# dual_sampler-GND-added.net
KiCad netlist of a schematic drawn in EAGLE
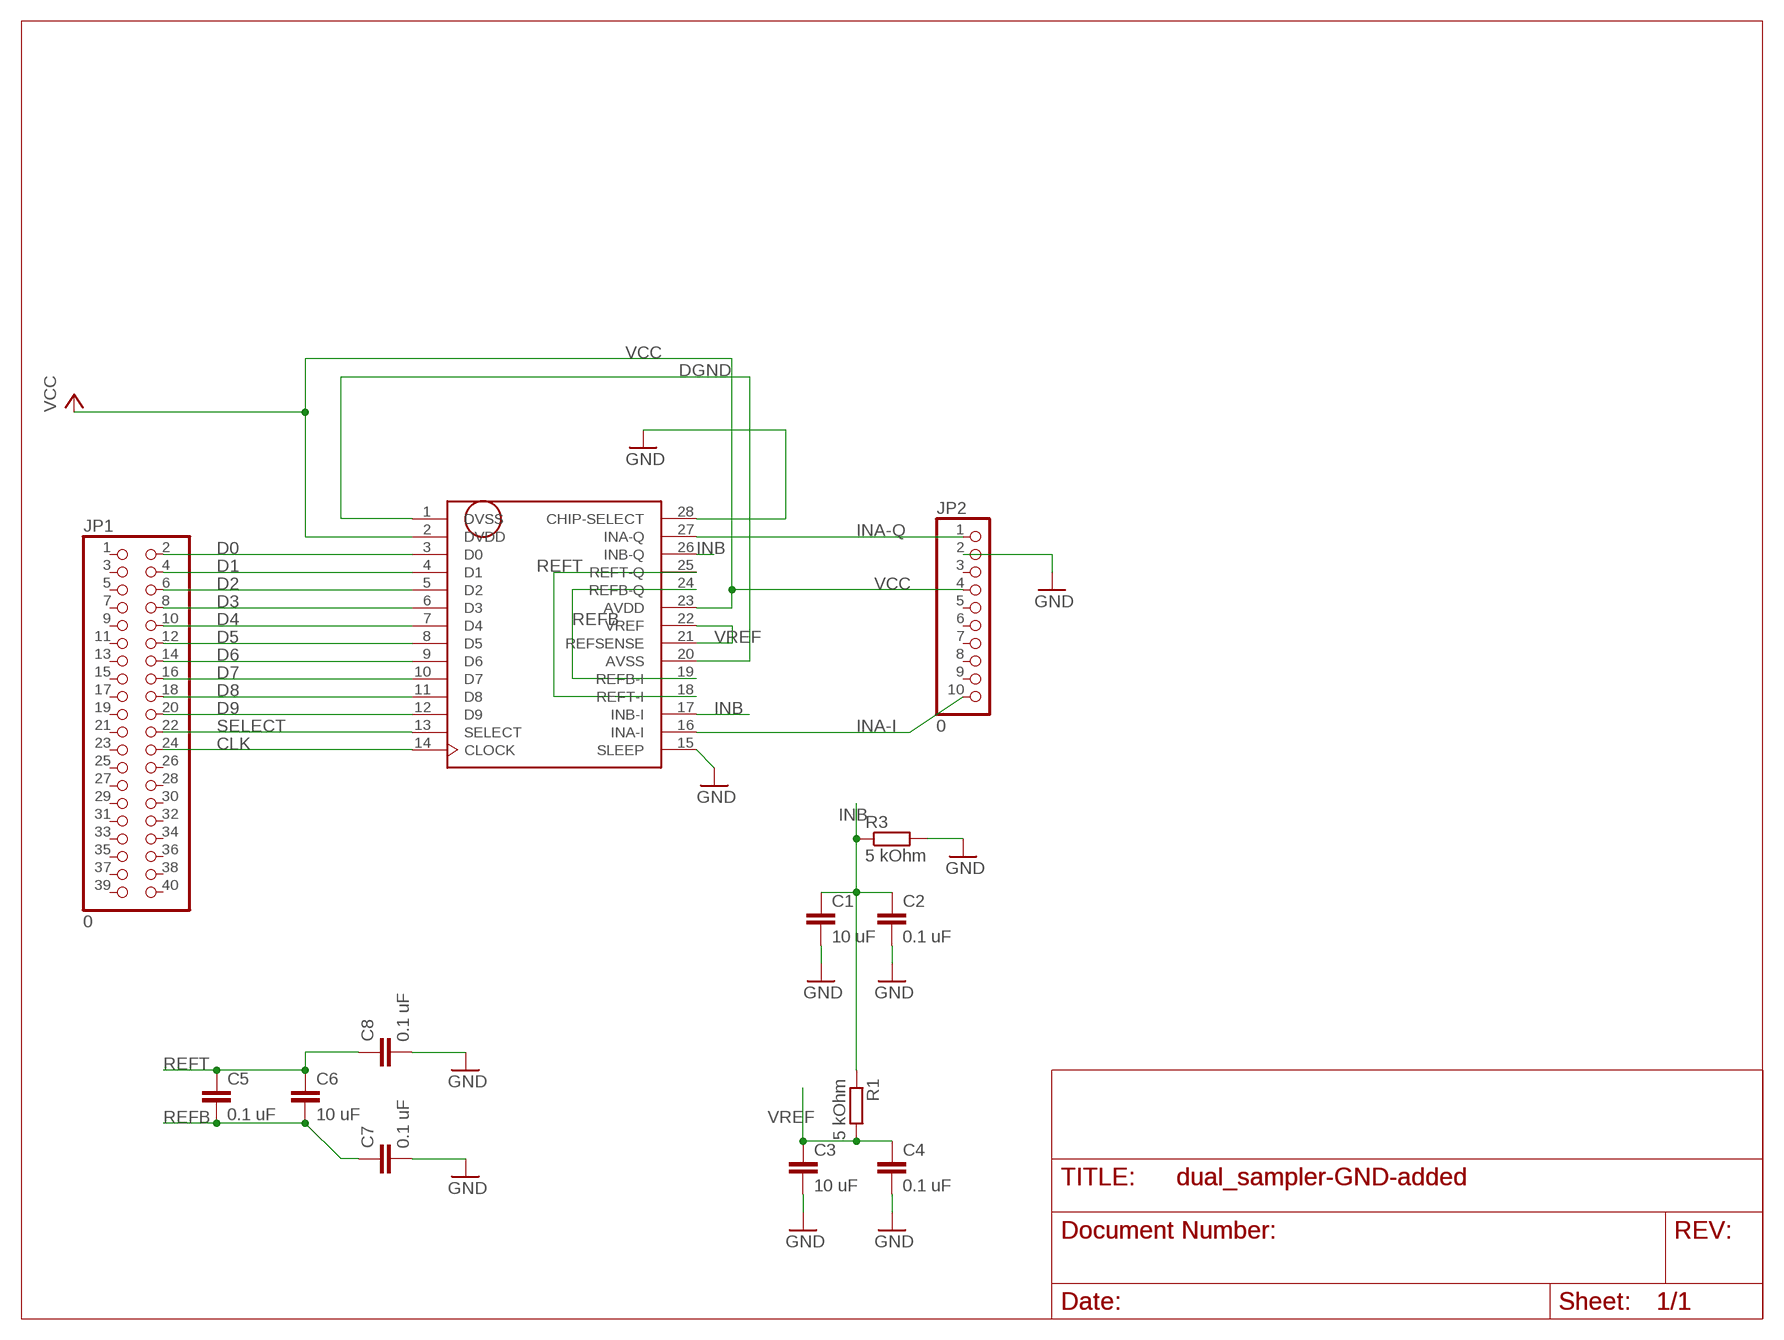
[diagram p0: schematic, sheet 1]

(export (version "E")
  (design (tool "Eeschema 10.0.6"))
  (components
    (comp (ref "C1")
      (value "10 uF")
      (footprint "eagle-import:C2.5-3")
      (libsource (lib "eagle-import") (part "C2,5-3"))
    )
    (comp (ref "C2")
      (value "0.1 uF")
      (footprint "eagle-import:C2.5-3")
      (libsource (lib "eagle-import") (part "C2,5-3"))
    )
    (comp (ref "C3")
      (value "10 uF")
      (footprint "eagle-import:C2.5-3")
      (libsource (lib "eagle-import") (part "C2,5-3"))
    )
    (comp (ref "C4")
      (value "0.1 uF")
      (footprint "eagle-import:C2.5-3")
      (libsource (lib "eagle-import") (part "C2,5-3"))
    )
    (comp (ref "C5")
      (value "0.1 uF")
      (footprint "eagle-import:C2.5-3")
      (libsource (lib "eagle-import") (part "C2,5-3"))
    )
    (comp (ref "C6")
      (value "10 uF")
      (footprint "eagle-import:C2.5-3")
      (libsource (lib "eagle-import") (part "C2,5-3"))
    )
    (comp (ref "C7")
      (value "0.1 uF")
      (footprint "eagle-import:C2.5-3")
      (libsource (lib "eagle-import") (part "C2,5-3"))
    )
    (comp (ref "C8")
      (value "0.1 uF")
      (footprint "eagle-import:C2.5-3")
      (libsource (lib "eagle-import") (part "C2,5-3"))
    )
    (comp (ref "JP1")
      (value "0")
      (footprint "eagle-import:2X20")
      (libsource (lib "eagle-import") (part "PINHD-2X20"))
    )
    (comp (ref "JP2")
      (value "0")
      (footprint "eagle-import:1X10")
      (libsource (lib "eagle-import") (part "PINHD-1X10"))
    )
    (comp (ref "R1")
      (value "5 kOhm")
      (footprint "eagle-import:0204_7")
      (libsource (lib "eagle-import") (part "R-EU_0204/7"))
    )
    (comp (ref "R3")
      (value "5 kOhm")
      (footprint "eagle-import:0204_7")
      (libsource (lib "eagle-import") (part "R-EU_0204/7"))
    )
    (comp (ref "U$1")
      (value "AD9201ARSZ")
      (footprint "eagle-import:SSOP28")
      (libsource (lib "eagle-import") (part "AD9201ARSZ"))
    )
  )
  (nets
    (net (code "1") (name "/CLK") (class "Default")
      (node (ref "JP1") (pin "24") (pinfunction "24_24") (pintype "passive"))
      (node (ref "U$1") (pin "14") (pinfunction "CLOCK_14") (pintype "input"))
    )
    (net (code "2") (name "/D0") (class "Default")
      (node (ref "JP1") (pin "2") (pinfunction "2_2") (pintype "passive"))
      (node (ref "U$1") (pin "3") (pinfunction "D0_3") (pintype "output"))
    )
    (net (code "3") (name "/D1") (class "Default")
      (node (ref "JP1") (pin "4") (pinfunction "4_4") (pintype "passive"))
      (node (ref "U$1") (pin "4") (pinfunction "D1_4") (pintype "output"))
    )
    (net (code "4") (name "/D2") (class "Default")
      (node (ref "JP1") (pin "6") (pinfunction "6_6") (pintype "passive"))
      (node (ref "U$1") (pin "5") (pinfunction "D2_5") (pintype "output"))
    )
    (net (code "5") (name "/D3") (class "Default")
      (node (ref "JP1") (pin "8") (pinfunction "8_8") (pintype "passive"))
      (node (ref "U$1") (pin "6") (pinfunction "D3_6") (pintype "output"))
    )
    (net (code "6") (name "/D4") (class "Default")
      (node (ref "JP1") (pin "10") (pinfunction "10_10") (pintype "passive"))
      (node (ref "U$1") (pin "7") (pinfunction "D4_7") (pintype "output"))
    )
    (net (code "7") (name "/D5") (class "Default")
      (node (ref "JP1") (pin "12") (pinfunction "12_12") (pintype "passive"))
      (node (ref "U$1") (pin "8") (pinfunction "D5_8") (pintype "output"))
    )
    (net (code "8") (name "/D6") (class "Default")
      (node (ref "JP1") (pin "14") (pinfunction "14_14") (pintype "passive"))
      (node (ref "U$1") (pin "9") (pinfunction "D6_9") (pintype "output"))
    )
    (net (code "9") (name "/D7") (class "Default")
      (node (ref "JP1") (pin "16") (pinfunction "16_16") (pintype "passive"))
      (node (ref "U$1") (pin "10") (pinfunction "D7_10") (pintype "output"))
    )
    (net (code "10") (name "/D8") (class "Default")
      (node (ref "JP1") (pin "18") (pinfunction "18_18") (pintype "passive"))
      (node (ref "U$1") (pin "11") (pinfunction "D8_11") (pintype "output"))
    )
    (net (code "11") (name "/D9") (class "Default")
      (node (ref "JP1") (pin "20") (pinfunction "20_20") (pintype "passive"))
      (node (ref "U$1") (pin "12") (pinfunction "D9_12") (pintype "output"))
    )
    (net (code "12") (name "/DGND") (class "Default")
      (node (ref "U$1") (pin "1") (pinfunction "DVSS_1") (pintype "power_in"))
      (node (ref "U$1") (pin "20") (pinfunction "AVSS_20") (pintype "input"))
    )
    (net (code "13") (name "/INA-I") (class "Default")
      (node (ref "JP2") (pin "10") (pinfunction "10_10") (pintype "passive"))
      (node (ref "U$1") (pin "16") (pinfunction "INA-I_16") (pintype "input"))
    )
    (net (code "14") (name "/INA-Q") (class "Default")
      (node (ref "JP2") (pin "1") (pinfunction "1_1") (pintype "passive"))
      (node (ref "U$1") (pin "27") (pinfunction "INA-Q_27") (pintype "input"))
    )
    (net (code "15") (name "/INB") (class "Default")
      (node (ref "C1") (pin "1") (pinfunction "1_1") (pintype "passive"))
      (node (ref "C2") (pin "1") (pinfunction "1_1") (pintype "passive"))
      (node (ref "R1") (pin "1") (pinfunction "1_1") (pintype "passive"))
      (node (ref "R3") (pin "1") (pinfunction "1_1") (pintype "passive"))
      (node (ref "U$1") (pin "17") (pinfunction "INB-I_17") (pintype "input"))
      (node (ref "U$1") (pin "26") (pinfunction "INB-Q_26") (pintype "input"))
    )
    (net (code "16") (name "/REFB") (class "Default")
      (node (ref "C5") (pin "2") (pinfunction "2_2") (pintype "passive"))
      (node (ref "C6") (pin "2") (pinfunction "2_2") (pintype "passive"))
      (node (ref "C7") (pin "1") (pinfunction "1_1") (pintype "passive"))
      (node (ref "U$1") (pin "19") (pinfunction "REFB-I_19") (pintype "bidirectional"))
      (node (ref "U$1") (pin "24") (pinfunction "REFB-Q_24") (pintype "input"))
    )
    (net (code "17") (name "/REFT") (class "Default")
      (node (ref "C5") (pin "1") (pinfunction "1_1") (pintype "passive"))
      (node (ref "C6") (pin "1") (pinfunction "1_1") (pintype "passive"))
      (node (ref "C8") (pin "1") (pinfunction "1_1") (pintype "passive"))
      (node (ref "U$1") (pin "18") (pinfunction "REFT-I_18") (pintype "input"))
      (node (ref "U$1") (pin "25") (pinfunction "REFT-Q_25") (pintype "input"))
    )
    (net (code "18") (name "/SELECT") (class "Default")
      (node (ref "JP1") (pin "22") (pinfunction "22_22") (pintype "passive"))
      (node (ref "U$1") (pin "13") (pinfunction "SELECT_13") (pintype "input"))
    )
    (net (code "19") (name "/VREF") (class "Default")
      (node (ref "C3") (pin "1") (pinfunction "1_1") (pintype "passive"))
      (node (ref "C4") (pin "1") (pinfunction "1_1") (pintype "passive"))
      (node (ref "R1") (pin "2") (pinfunction "2_2") (pintype "passive"))
      (node (ref "U$1") (pin "21") (pinfunction "REFSENSE_21") (pintype "input"))
      (node (ref "U$1") (pin "22") (pinfunction "VREF_22") (pintype "input"))
    )
    (net (code "20") (name "GND") (class "Default")
      (node (ref "C1") (pin "2") (pinfunction "2_2") (pintype "passive"))
      (node (ref "C2") (pin "2") (pinfunction "2_2") (pintype "passive"))
      (node (ref "C3") (pin "2") (pinfunction "2_2") (pintype "passive"))
      (node (ref "C4") (pin "2") (pinfunction "2_2") (pintype "passive"))
      (node (ref "C7") (pin "2") (pinfunction "2_2") (pintype "passive"))
      (node (ref "C8") (pin "2") (pinfunction "2_2") (pintype "passive"))
      (node (ref "JP2") (pin "2") (pinfunction "2_2") (pintype "passive"))
      (node (ref "R3") (pin "2") (pinfunction "2_2") (pintype "passive"))
      (node (ref "U$1") (pin "15") (pinfunction "SLEEP_15") (pintype "input"))
      (node (ref "U$1") (pin "28") (pinfunction "CHIP-SELECT_28") (pintype "input"))
    )
    (net (code "21") (name "VCC") (class "Default")
      (node (ref "JP2") (pin "4") (pinfunction "4_4") (pintype "passive"))
      (node (ref "U$1") (pin "2") (pinfunction "DVDD_2") (pintype "power_in"))
      (node (ref "U$1") (pin "23") (pinfunction "AVDD_23") (pintype "power_in"))
    )
    (net (code "22") (name "unconnected-(JP1-Pad1)") (class "Default")
      (node (ref "JP1") (pin "1") (pinfunction "1_1") (pintype "passive"))
    )
    (net (code "23") (name "unconnected-(JP1-Pad3)") (class "Default")
      (node (ref "JP1") (pin "3") (pinfunction "3_3") (pintype "passive"))
    )
    (net (code "24") (name "unconnected-(JP1-Pad5)") (class "Default")
      (node (ref "JP1") (pin "5") (pinfunction "5_5") (pintype "passive"))
    )
    (net (code "25") (name "unconnected-(JP1-Pad7)") (class "Default")
      (node (ref "JP1") (pin "7") (pinfunction "7_7") (pintype "passive"))
    )
    (net (code "26") (name "unconnected-(JP1-Pad9)") (class "Default")
      (node (ref "JP1") (pin "9") (pinfunction "9_9") (pintype "passive"))
    )
    (net (code "27") (name "unconnected-(JP1-Pad11)") (class "Default")
      (node (ref "JP1") (pin "11") (pinfunction "11_11") (pintype "passive"))
    )
    (net (code "28") (name "unconnected-(JP1-Pad13)") (class "Default")
      (node (ref "JP1") (pin "13") (pinfunction "13_13") (pintype "passive"))
    )
    (net (code "29") (name "unconnected-(JP1-Pad15)") (class "Default")
      (node (ref "JP1") (pin "15") (pinfunction "15_15") (pintype "passive"))
    )
    (net (code "30") (name "unconnected-(JP1-Pad17)") (class "Default")
      (node (ref "JP1") (pin "17") (pinfunction "17_17") (pintype "passive"))
    )
    (net (code "31") (name "unconnected-(JP1-Pad19)") (class "Default")
      (node (ref "JP1") (pin "19") (pinfunction "19_19") (pintype "passive"))
    )
    (net (code "32") (name "unconnected-(JP1-Pad21)") (class "Default")
      (node (ref "JP1") (pin "21") (pinfunction "21_21") (pintype "passive"))
    )
    (net (code "33") (name "unconnected-(JP1-Pad23)") (class "Default")
      (node (ref "JP1") (pin "23") (pinfunction "23_23") (pintype "passive"))
    )
    (net (code "34") (name "unconnected-(JP1-Pad25)") (class "Default")
      (node (ref "JP1") (pin "25") (pinfunction "25_25") (pintype "passive"))
    )
    (net (code "35") (name "unconnected-(JP1-Pad26)") (class "Default")
      (node (ref "JP1") (pin "26") (pinfunction "26_26") (pintype "passive"))
    )
    (net (code "36") (name "unconnected-(JP1-Pad27)") (class "Default")
      (node (ref "JP1") (pin "27") (pinfunction "27_27") (pintype "passive"))
    )
    (net (code "37") (name "unconnected-(JP1-Pad28)") (class "Default")
      (node (ref "JP1") (pin "28") (pinfunction "28_28") (pintype "passive"))
    )
    (net (code "38") (name "unconnected-(JP1-Pad29)") (class "Default")
      (node (ref "JP1") (pin "29") (pinfunction "29_29") (pintype "passive"))
    )
    (net (code "39") (name "unconnected-(JP1-Pad30)") (class "Default")
      (node (ref "JP1") (pin "30") (pinfunction "30_30") (pintype "passive"))
    )
    (net (code "40") (name "unconnected-(JP1-Pad31)") (class "Default")
      (node (ref "JP1") (pin "31") (pinfunction "31_31") (pintype "passive"))
    )
    (net (code "41") (name "unconnected-(JP1-Pad32)") (class "Default")
      (node (ref "JP1") (pin "32") (pinfunction "32_32") (pintype "passive"))
    )
    (net (code "42") (name "unconnected-(JP1-Pad33)") (class "Default")
      (node (ref "JP1") (pin "33") (pinfunction "33_33") (pintype "passive"))
    )
    (net (code "43") (name "unconnected-(JP1-Pad34)") (class "Default")
      (node (ref "JP1") (pin "34") (pinfunction "34_34") (pintype "passive"))
    )
    (net (code "44") (name "unconnected-(JP1-Pad35)") (class "Default")
      (node (ref "JP1") (pin "35") (pinfunction "35_35") (pintype "passive"))
    )
    (net (code "45") (name "unconnected-(JP1-Pad36)") (class "Default")
      (node (ref "JP1") (pin "36") (pinfunction "36_36") (pintype "passive"))
    )
    (net (code "46") (name "unconnected-(JP1-Pad37)") (class "Default")
      (node (ref "JP1") (pin "37") (pinfunction "37_37") (pintype "passive"))
    )
    (net (code "47") (name "unconnected-(JP1-Pad38)") (class "Default")
      (node (ref "JP1") (pin "38") (pinfunction "38_38") (pintype "passive"))
    )
    (net (code "48") (name "unconnected-(JP1-Pad39)") (class "Default")
      (node (ref "JP1") (pin "39") (pinfunction "39_39") (pintype "passive"))
    )
    (net (code "49") (name "unconnected-(JP1-Pad40)") (class "Default")
      (node (ref "JP1") (pin "40") (pinfunction "40_40") (pintype "passive"))
    )
    (net (code "50") (name "unconnected-(JP2-Pad3)") (class "Default")
      (node (ref "JP2") (pin "3") (pinfunction "3_3") (pintype "passive"))
    )
    (net (code "51") (name "unconnected-(JP2-Pad5)") (class "Default")
      (node (ref "JP2") (pin "5") (pinfunction "5_5") (pintype "passive"))
    )
    (net (code "52") (name "unconnected-(JP2-Pad6)") (class "Default")
      (node (ref "JP2") (pin "6") (pinfunction "6_6") (pintype "passive"))
    )
    (net (code "53") (name "unconnected-(JP2-Pad7)") (class "Default")
      (node (ref "JP2") (pin "7") (pinfunction "7_7") (pintype "passive"))
    )
    (net (code "54") (name "unconnected-(JP2-Pad8)") (class "Default")
      (node (ref "JP2") (pin "8") (pinfunction "8_8") (pintype "passive"))
    )
    (net (code "55") (name "unconnected-(JP2-Pad9)") (class "Default")
      (node (ref "JP2") (pin "9") (pinfunction "9_9") (pintype "passive"))
    )
  )
)
